# RAK11720.net
KiCad netlist of a schematic drawn in Altium Designer
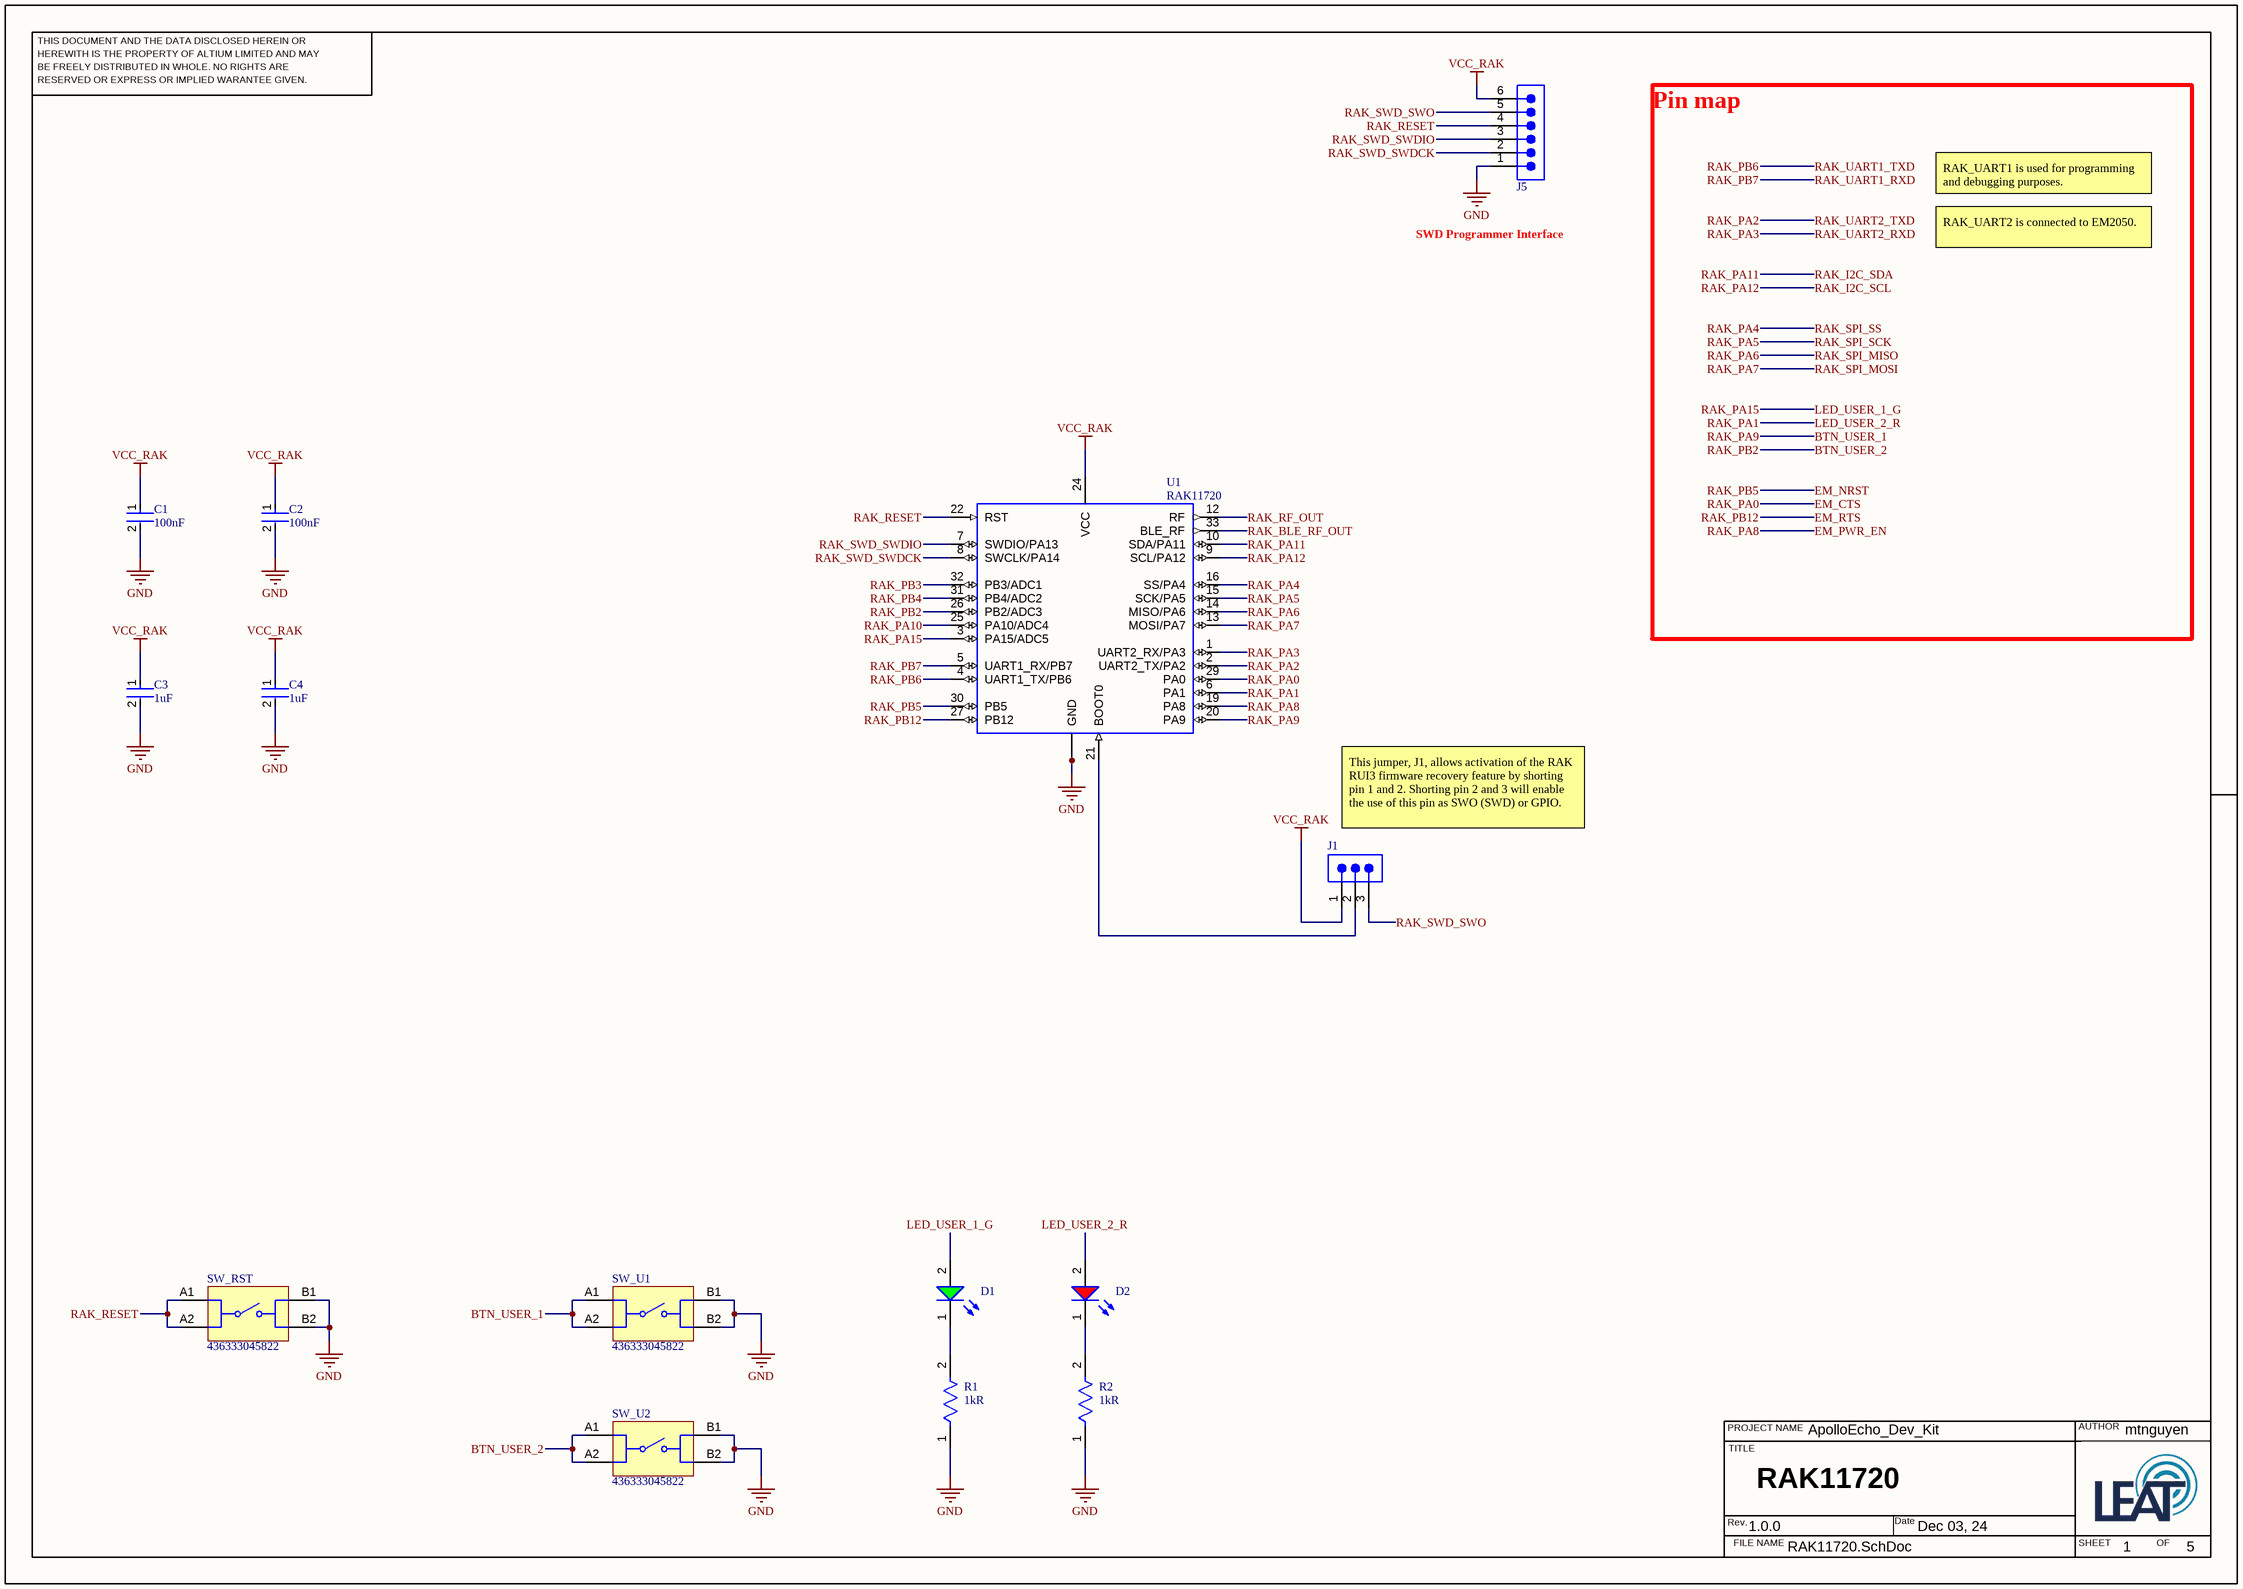
[diagram p0: RAK11720.SchDoc]

(export (version "E")
  (design (tool "Eeschema 10.0.6"))
  (components
    (comp (ref "C1")
      (value "0402ZD104KAT2A")
      (footprint "FP-0402-L_1_0_1-W_0_5_0_1-IPC_C")
      (description "General Purpose Ceramic Capacitor, 0402, 100nF, 10%, X5R, 15%, 10V")
      (fields
        (field (name "VOLTAGE") "10V")
        (field (name "TOLERANCE") "10%")
        (field (name "CAPACITANCE") "100nF")
      )
      (libsource (lib "Altium Content Vault") (part "b4654b650e69147ec39a6b967a45e02"))
    )
    (comp (ref "C2")
      (value "0402ZD104KAT2A")
      (footprint "FP-0402-L_1_0_1-W_0_5_0_1-IPC_C")
      (description "General Purpose Ceramic Capacitor, 0402, 100nF, 10%, X5R, 15%, 10V")
      (fields
        (field (name "VOLTAGE") "10V")
        (field (name "TOLERANCE") "10%")
        (field (name "CAPACITANCE") "100nF")
      )
      (libsource (lib "Altium Content Vault") (part "b4654b650e69147ec39a6b967a45e02"))
    )
    (comp (ref "C3")
      (value "EMK105BJ105KV-F")
      (footprint "FP-0402-L_1_0_0_05-W_0_5-IPC_A")
      (description "None")
      (fields (field (name "TOLERANCE") "10%") (field (name "CAPACITANCE") "1uF"))
      (libsource (lib "Altium Content Vault") (part "b4654b650e69147ec39a6b967a45e02"))
    )
    (comp (ref "C4")
      (value "EMK105BJ105KV-F")
      (footprint "FP-0402-L_1_0_0_05-W_0_5-IPC_A")
      (description "None")
      (fields (field (name "TOLERANCE") "10%") (field (name "CAPACITANCE") "1uF"))
      (libsource (lib "Altium Content Vault") (part "b4654b650e69147ec39a6b967a45e02"))
    )
    (comp (ref "D1")
      (value "150060VS75000")
      (footprint "WL-SMCW_0603_150060xx75000")
      (description "WURTH ELEKTRONIK - 150060VS75000 - LED, Green, SMD, 0603, 30 mA, 2 V, 570 nm")
      (libsource (lib "Altium Content Vault") (part "LED_Green_2A-1K"))
    )
    (comp (ref "D2")
      (value "150060RS75000")
      (footprint "WL-SMCW_0603_150060xx75000")
      (description "LED Low-Power Uni-Color Red 630nm 2V 2-Pin Chip 0603(1608Metric) T/R")
      (libsource (lib "Altium Content Vault") (part "LED_Red_2A-1K"))
    )
    (comp (ref "J1")
      (value "61300311121")
      (footprint "61300311121")
      (libsource (lib "Altium Content Vault") (part "Header_Male_1R_03P"))
    )
    (comp (ref "J5")
      (value "61300611121")
      (footprint "61300611121")
      (libsource (lib "Altium Content Vault") (part "Header_Male_1R_06P"))
    )
    (comp (ref "R1")
      (value "RMCF0402FT1K00")
      (footprint "FP-RMCF0402-IPC_A")
      (description "1kΩ ±1% 0.063W 0402 Thick Film Chip Resistor AEC-Q200 compliant")
      (fields (field (name "TOLERANCE") "1%") (field (name "RESISTANCE") "1kR"))
      (libsource (lib "Altium Content Vault") (part "1029c3af85768c4190bb7ad29bc67b5"))
    )
    (comp (ref "R2")
      (value "RMCF0402FT1K00")
      (footprint "FP-RMCF0402-IPC_A")
      (description "1kΩ ±1% 0.063W 0402 Thick Film Chip Resistor AEC-Q200 compliant")
      (fields (field (name "TOLERANCE") "1%") (field (name "RESISTANCE") "1kR"))
      (libsource (lib "Altium Content Vault") (part "1029c3af85768c4190bb7ad29bc67b5"))
    )
    (comp (ref "SW_RST")
      (value "436333045822")
      (footprint "436333045822")
      (libsource (lib "Altium Content Vault") (part "SPST-NO_4P"))
    )
    (comp (ref "SW_U1")
      (value "436333045822")
      (footprint "436333045822")
      (libsource (lib "Altium Content Vault") (part "SPST-NO_4P"))
    )
    (comp (ref "SW_U2")
      (value "436333045822")
      (footprint "436333045822")
      (libsource (lib "Altium Content Vault") (part "SPST-NO_4P"))
    )
    (comp (ref "U1")
      (value "RAK11720")
      (footprint "RAK11720")
      (description "RAK11720 Ambiq Apollo3 Blue SX1262 LoRa Bluetooth Module for LoRaWAN")
      (fields (field (name "MP") "RAK3172") (field (name "MF") "Shenzhen RAKwireless Technology Co.,Ltd."))
      (libsource (lib "RAK3172") (part "RAK11720"))
    )
  )
  (nets
    (net (code "1") (name "/BTN_USER_1") (class "Default")
      (node (ref "SW_U1") (pin "A1") (pinfunction "A1_A1") (pintype "passive"))
      (node (ref "SW_U1") (pin "A2") (pinfunction "A2_A2") (pintype "passive"))
      (node (ref "U1") (pin "20") (pinfunction "PA9_20") (pintype "bidirectional"))
    )
    (net (code "2") (name "/BTN_USER_2") (class "Default")
      (node (ref "SW_U2") (pin "A1") (pinfunction "A1_A1") (pintype "passive"))
      (node (ref "SW_U2") (pin "A2") (pinfunction "A2_A2") (pintype "passive"))
      (node (ref "U1") (pin "26") (pinfunction "PB2/ADC3_26") (pintype "bidirectional"))
    )
    (net (code "3") (name "/EM_CTS") (class "Default")
      (node (ref "U1") (pin "29") (pinfunction "PA0_29") (pintype "bidirectional"))
    )
    (net (code "4") (name "/EM_NRST") (class "Default")
      (node (ref "U1") (pin "30") (pinfunction "PB5_30") (pintype "bidirectional"))
    )
    (net (code "5") (name "/EM_PWR_EN") (class "Default")
      (node (ref "U1") (pin "19") (pinfunction "PA8_19") (pintype "bidirectional"))
    )
    (net (code "6") (name "/EM_RTS") (class "Default")
      (node (ref "U1") (pin "27") (pinfunction "PB12_27") (pintype "bidirectional"))
    )
    (net (code "7") (name "/LED_USER_1_G") (class "Default")
      (node (ref "D1") (pin "2") (pinfunction "A_2") (pintype "passive"))
      (node (ref "U1") (pin "3") (pinfunction "PA15/ADC5_3") (pintype "bidirectional"))
    )
    (net (code "8") (name "/LED_USER_2_R") (class "Default")
      (node (ref "D2") (pin "2") (pinfunction "A_2") (pintype "passive"))
      (node (ref "U1") (pin "6") (pinfunction "PA1_6") (pintype "bidirectional"))
    )
    (net (code "9") (name "/RAK_BLE_RF_OUT") (class "Default")
      (node (ref "U1") (pin "33") (pinfunction "BLE_RF_33") (pintype "output"))
    )
    (net (code "10") (name "/RAK_I2C_SCL") (class "Default")
      (node (ref "U1") (pin "9") (pinfunction "SCL/PA12_9") (pintype "bidirectional"))
    )
    (net (code "11") (name "/RAK_I2C_SDA") (class "Default")
      (node (ref "U1") (pin "10") (pinfunction "SDA/PA11_10") (pintype "bidirectional"))
    )
    (net (code "12") (name "/RAK_PA2") (class "Default")
      (node (ref "U1") (pin "2") (pinfunction "UART2_TX/PA2_2") (pintype "bidirectional"))
    )
    (net (code "13") (name "/RAK_PA3") (class "Default")
      (node (ref "U1") (pin "1") (pinfunction "UART2_RX/PA3_1") (pintype "bidirectional"))
    )
    (net (code "14") (name "/RAK_PA4") (class "Default")
      (node (ref "U1") (pin "16") (pinfunction "SS/PA4_16") (pintype "bidirectional"))
    )
    (net (code "15") (name "/RAK_PA5") (class "Default")
      (node (ref "U1") (pin "15") (pinfunction "SCK/PA5_15") (pintype "bidirectional"))
    )
    (net (code "16") (name "/RAK_PA6") (class "Default")
      (node (ref "U1") (pin "14") (pinfunction "MISO/PA6_14") (pintype "bidirectional"))
    )
    (net (code "17") (name "/RAK_PA7") (class "Default")
      (node (ref "U1") (pin "13") (pinfunction "MOSI/PA7_13") (pintype "bidirectional"))
    )
    (net (code "18") (name "/RAK_PA10") (class "Default")
      (node (ref "U1") (pin "25") (pinfunction "PA10/ADC4_25") (pintype "bidirectional"))
    )
    (net (code "19") (name "/RAK_PB3") (class "Default")
      (node (ref "U1") (pin "32") (pinfunction "PB3/ADC1_32") (pintype "bidirectional"))
    )
    (net (code "20") (name "/RAK_PB4") (class "Default")
      (node (ref "U1") (pin "31") (pinfunction "PB4/ADC2_31") (pintype "bidirectional"))
    )
    (net (code "21") (name "/RAK_PB6") (class "Default")
      (node (ref "U1") (pin "4") (pinfunction "UART1_TX/PB6_4") (pintype "bidirectional"))
    )
    (net (code "22") (name "/RAK_PB7") (class "Default")
      (node (ref "U1") (pin "5") (pinfunction "UART1_RX/PB7_5") (pintype "bidirectional"))
    )
    (net (code "23") (name "/RAK_RESET") (class "Default")
      (node (ref "J5") (pin "4") (pinfunction "4_4") (pintype "passive"))
      (node (ref "SW_RST") (pin "A1") (pinfunction "A1_A1") (pintype "passive"))
      (node (ref "SW_RST") (pin "A2") (pinfunction "A2_A2") (pintype "passive"))
      (node (ref "U1") (pin "22") (pinfunction "RST_22") (pintype "input"))
    )
    (net (code "24") (name "/RAK_RF_OUT") (class "Default")
      (node (ref "U1") (pin "12") (pinfunction "RF_12") (pintype "output"))
    )
    (net (code "25") (name "/RAK_SWD_SWDCK") (class "Default")
      (node (ref "J5") (pin "2") (pinfunction "2_2") (pintype "passive"))
      (node (ref "U1") (pin "8") (pinfunction "SWCLK/PA14_8") (pintype "bidirectional"))
    )
    (net (code "26") (name "/RAK_SWD_SWDIO") (class "Default")
      (node (ref "J5") (pin "3") (pinfunction "3_3") (pintype "passive"))
      (node (ref "U1") (pin "7") (pinfunction "SWDIO/PA13_7") (pintype "bidirectional"))
    )
    (net (code "27") (name "/RAK_SWD_SWO") (class "Default")
      (node (ref "J1") (pin "3") (pinfunction "3_3") (pintype "passive"))
      (node (ref "J5") (pin "5") (pinfunction "5_5") (pintype "passive"))
    )
    (net (code "28") (name "GND") (class "Default")
      (node (ref "C1") (pin "2") (pinfunction "2_2") (pintype "passive"))
      (node (ref "C2") (pin "2") (pinfunction "2_2") (pintype "passive"))
      (node (ref "C3") (pin "2") (pinfunction "2_2") (pintype "passive"))
      (node (ref "C4") (pin "2") (pinfunction "2_2") (pintype "passive"))
      (node (ref "J5") (pin "1") (pinfunction "1_1") (pintype "passive"))
      (node (ref "R1") (pin "1") (pinfunction "1_1") (pintype "passive"))
      (node (ref "R2") (pin "1") (pinfunction "1_1") (pintype "passive"))
      (node (ref "SW_RST") (pin "B1") (pinfunction "B1_B1") (pintype "passive"))
      (node (ref "SW_RST") (pin "B2") (pinfunction "B2_B2") (pintype "passive"))
      (node (ref "SW_U1") (pin "B1") (pinfunction "B1_B1") (pintype "passive"))
      (node (ref "SW_U1") (pin "B2") (pinfunction "B2_B2") (pintype "passive"))
      (node (ref "SW_U2") (pin "B1") (pinfunction "B1_B1") (pintype "passive"))
      (node (ref "SW_U2") (pin "B2") (pinfunction "B2_B2") (pintype "passive"))
      (node (ref "U1") (pin "11") (pinfunction "GND_11") (pintype "power_in"))
      (node (ref "U1") (pin "17") (pinfunction "GND_17") (pintype "power_in"))
      (node (ref "U1") (pin "18") (pinfunction "GND_18") (pintype "power_in"))
      (node (ref "U1") (pin "23") (pinfunction "GND_23") (pintype "power_in"))
      (node (ref "U1") (pin "28") (pinfunction "GND_28") (pintype "power_in"))
      (node (ref "U1") (pin "34") (pinfunction "GND_34") (pintype "power_in"))
    )
    (net (code "29") (name "Net-(D1-K)") (class "Default")
      (node (ref "D1") (pin "1") (pinfunction "K_1") (pintype "passive"))
      (node (ref "R1") (pin "2") (pinfunction "2_2") (pintype "passive"))
    )
    (net (code "30") (name "Net-(D2-K)") (class "Default")
      (node (ref "D2") (pin "1") (pinfunction "K_1") (pintype "passive"))
      (node (ref "R2") (pin "2") (pinfunction "2_2") (pintype "passive"))
    )
    (net (code "31") (name "Net-(U1-BOOT0)") (class "Default")
      (node (ref "J1") (pin "2") (pinfunction "2_2") (pintype "passive"))
      (node (ref "U1") (pin "21") (pinfunction "BOOT0_21") (pintype "input"))
    )
    (net (code "32") (name "VCC_RAK") (class "Default")
      (node (ref "C1") (pin "1") (pinfunction "1_1") (pintype "passive"))
      (node (ref "C2") (pin "1") (pinfunction "1_1") (pintype "passive"))
      (node (ref "C3") (pin "1") (pinfunction "1_1") (pintype "passive"))
      (node (ref "C4") (pin "1") (pinfunction "1_1") (pintype "passive"))
      (node (ref "J1") (pin "1") (pinfunction "1_1") (pintype "passive"))
      (node (ref "J5") (pin "6") (pinfunction "6_6") (pintype "passive"))
      (node (ref "U1") (pin "24") (pinfunction "VCC_24") (pintype "power_in"))
    )
  )
)
